# MCU.net
KiCad netlist of a schematic drawn in Altium Designer
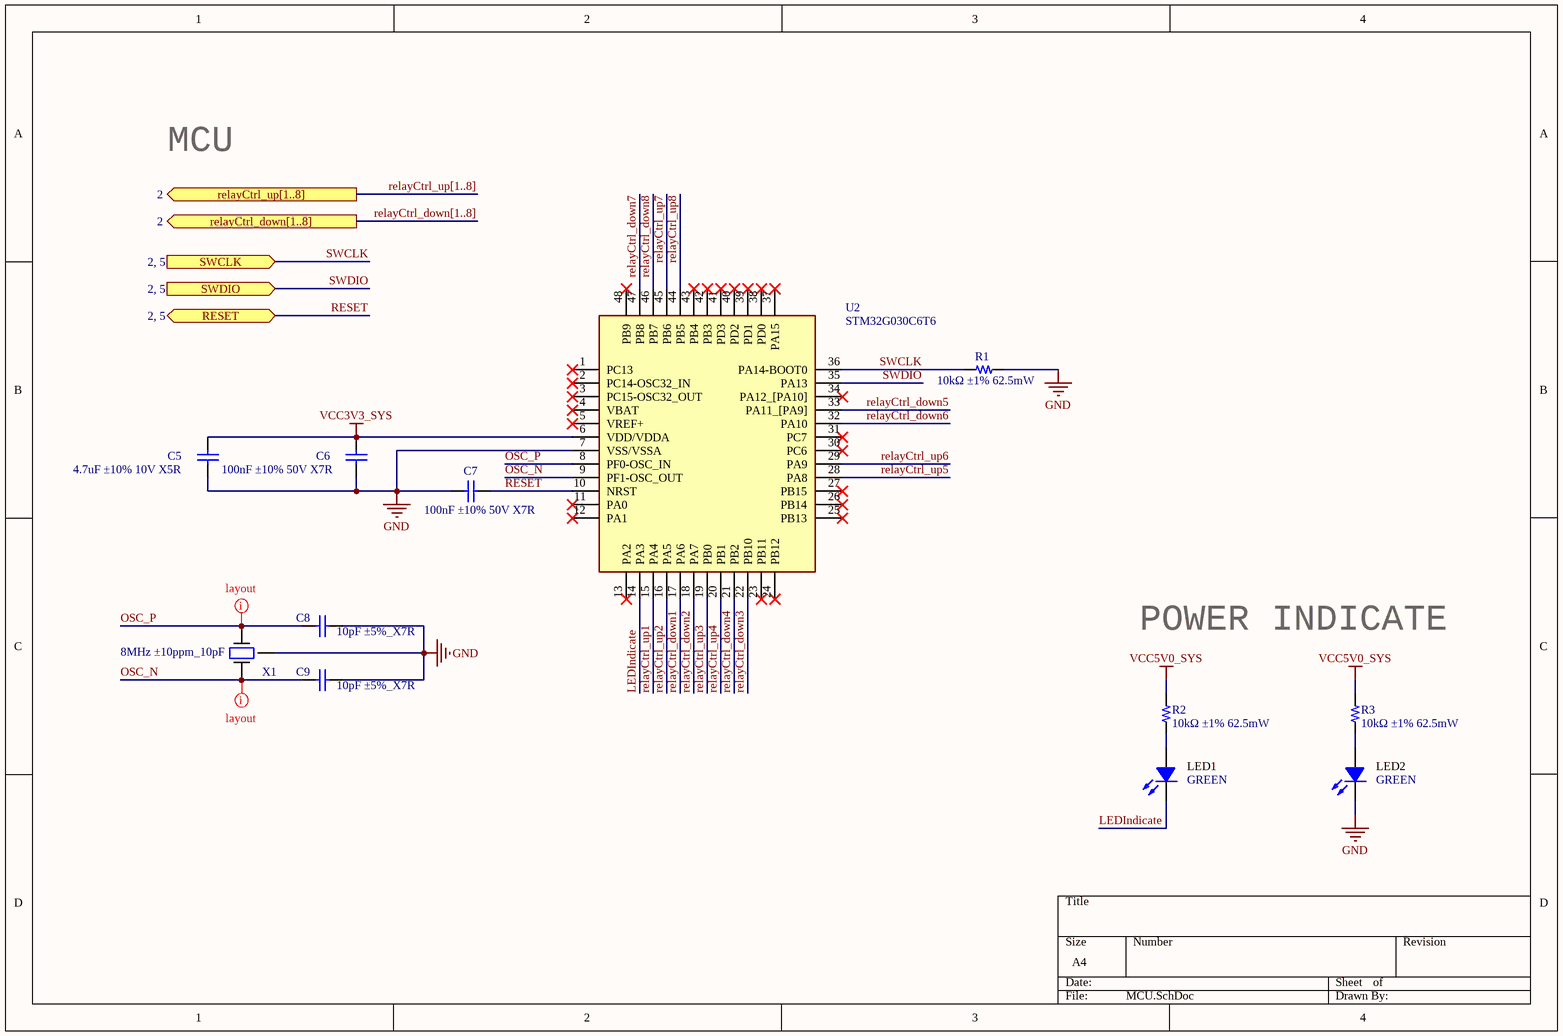
[diagram p0: MCU.SchDoc]

(export (version "E")
  (design (tool "Eeschema 10.0.6"))
  (components
    (comp (ref "C5")
      (value "4.7uF ±10% 10V X5R")
      (footprint "C0402")
      (description "CL05A475KP5NRNC")
      (fields (field (name "PUBLISHER") "Altium Limited"))
      (libsource (lib "Component") (part "Cap"))
    )
    (comp (ref "C6")
      (value "100nF ±10% 50V X7R")
      (footprint "C0402")
      (description "CL05B104KO5NNNC")
      (fields (field (name "PUBLISHER") "Altium Limited"))
      (libsource (lib "Component") (part "Cap"))
    )
    (comp (ref "C7")
      (value "100nF ±10% 50V X7R")
      (footprint "C0402")
      (description "CL05B104KO5NNNC")
      (fields (field (name "PUBLISHER") "Altium Limited"))
      (libsource (lib "Component") (part "Cap"))
    )
    (comp (ref "C8")
      (value "10pF ±5%_X7R")
      (footprint "C0402")
      (description "Capacitor")
      (fields (field (name "PUBLISHER") "Altium Limited"))
      (libsource (lib "Component") (part "Cap"))
    )
    (comp (ref "C9")
      (value "10pF ±5%_X7R")
      (footprint "C0402")
      (description "Capacitor")
      (fields (field (name "PUBLISHER") "Altium Limited"))
      (libsource (lib "Component") (part "Cap"))
    )
    (comp (ref "LED1")
      (value "GREEN")
      (footprint "LED0603-RD")
      (fields
        (field (name "MANUFACTURER") "EVERLIGHT(亿光)")
        (field (name "MANUFACTURER PART") "17-21SURC/S530-A2/TR8")
      )
      (libsource (lib "Component") (part "LED"))
    )
    (comp (ref "LED2")
      (value "GREEN")
      (footprint "LED0603-RD")
      (fields
        (field (name "MANUFACTURER") "EVERLIGHT(亿光)")
        (field (name "MANUFACTURER PART") "17-21SURC/S530-A2/TR8")
      )
      (libsource (lib "Component") (part "LED"))
    )
    (comp (ref "R1")
      (value "10kΩ ±1% 62.5mW")
      (footprint "R0402")
      (description "0402WGF1002TCE")
      (libsource (lib "Device") (part "R-0603"))
    )
    (comp (ref "R2")
      (value "10kΩ ±1% 62.5mW")
      (footprint "R0402")
      (description "0402WGF1002TCE")
      (libsource (lib "Device") (part "R-0603"))
    )
    (comp (ref "R3")
      (value "10kΩ ±1% 62.5mW")
      (footprint "R0402")
      (description "0402WGF1002TCE")
      (libsource (lib "Device") (part "R-0603"))
    )
    (comp (ref "U2")
      (value "STM32G030C6T6")
      (footprint "SamacSys:QFP50P900X900X160-48N")
      (description "Integrated Circuit")
      (fields (field (name "MOUSER PART NUMBER") "511-STM32G030C6T6"))
      (libsource (lib "*") (part "STM32G030C6T6"))
    )
    (comp (ref "X1")
      (value "8MHz ±10ppm_10pF")
      (footprint "CRYSTAL_3225")
      (description "Crystal 8MHz ±10ppm 10pF 200 Ohm -10°C ~ 60°C Surface Mount 4-SMD, No Lead (DFN, LCC)")
      (fields
        (field (name "MANUFACTURER") "Abracon LLC")
        (field (name "MANUFACTURER PART NUMBER") "ABM3B-8.000MHZ-10-1-U-T")
      )
      (libsource (lib "Component") (part "CRYSTAL"))
    )
  )
  (nets
    (net (code "1") (name "/LEDIndicate") (class "Default")
      (node (ref "LED1") (pin "2") (pinfunction "K_2") (pintype "passive"))
      (node (ref "U2") (pin "14") (pinfunction "PA3_14") (pintype "passive"))
    )
    (net (code "2") (name "/OSC_N") (class "Default")
      (node (ref "C9") (pin "1") (pinfunction "1_1") (pintype "passive"))
      (node (ref "U2") (pin "9") (pinfunction "PF1-OSC_OUT_9") (pintype "passive"))
      (node (ref "X1") (pin "1") (pintype "passive"))
    )
    (net (code "3") (name "/OSC_P") (class "Default")
      (node (ref "C8") (pin "1") (pinfunction "1_1") (pintype "passive"))
      (node (ref "U2") (pin "8") (pinfunction "PF0-OSC_IN_8") (pintype "passive"))
      (node (ref "X1") (pin "3") (pintype "passive"))
    )
    (net (code "4") (name "/RESET") (class "Default")
      (node (ref "C7") (pin "2") (pinfunction "2_2") (pintype "passive"))
      (node (ref "U2") (pin "10") (pinfunction "NRST_10") (pintype "passive"))
    )
    (net (code "5") (name "/SWCLK") (class "Default")
      (node (ref "R1") (pin "2") (pinfunction "2_2") (pintype "passive"))
      (node (ref "U2") (pin "36") (pinfunction "PA14-BOOT0_36") (pintype "passive"))
    )
    (net (code "6") (name "/SWDIO") (class "Default")
      (node (ref "U2") (pin "35") (pinfunction "PA13_35") (pintype "passive"))
    )
    (net (code "7") (name "/relayCtrl_down1") (class "Default")
      (node (ref "U2") (pin "17") (pinfunction "PA6_17") (pintype "passive"))
    )
    (net (code "8") (name "/relayCtrl_down2") (class "Default")
      (node (ref "U2") (pin "18") (pinfunction "PA7_18") (pintype "passive"))
    )
    (net (code "9") (name "/relayCtrl_down3") (class "Default")
      (node (ref "U2") (pin "22") (pinfunction "PB10_22") (pintype "passive"))
    )
    (net (code "10") (name "/relayCtrl_down4") (class "Default")
      (node (ref "U2") (pin "21") (pinfunction "PB2_21") (pintype "passive"))
    )
    (net (code "11") (name "/relayCtrl_down5") (class "Default")
      (node (ref "U2") (pin "33") (pinfunction "PA11_[PA9]_33") (pintype "passive"))
    )
    (net (code "12") (name "/relayCtrl_down6") (class "Default")
      (node (ref "U2") (pin "32") (pinfunction "PA10_32") (pintype "passive"))
    )
    (net (code "13") (name "/relayCtrl_down7") (class "Default")
      (node (ref "U2") (pin "47") (pinfunction "PB8_47") (pintype "passive"))
    )
    (net (code "14") (name "/relayCtrl_down8") (class "Default")
      (node (ref "U2") (pin "46") (pinfunction "PB7_46") (pintype "passive"))
    )
    (net (code "16") (name "/relayCtrl_up1") (class "Default")
      (node (ref "U2") (pin "15") (pinfunction "PA4_15") (pintype "passive"))
    )
    (net (code "17") (name "/relayCtrl_up2") (class "Default")
      (node (ref "U2") (pin "16") (pinfunction "PA5_16") (pintype "passive"))
    )
    (net (code "18") (name "/relayCtrl_up3") (class "Default")
      (node (ref "U2") (pin "19") (pinfunction "PB0_19") (pintype "passive"))
    )
    (net (code "19") (name "/relayCtrl_up4") (class "Default")
      (node (ref "U2") (pin "20") (pinfunction "PB1_20") (pintype "passive"))
    )
    (net (code "20") (name "/relayCtrl_up5") (class "Default")
      (node (ref "U2") (pin "28") (pinfunction "PA8_28") (pintype "passive"))
    )
    (net (code "21") (name "/relayCtrl_up6") (class "Default")
      (node (ref "U2") (pin "29") (pinfunction "PA9_29") (pintype "passive"))
    )
    (net (code "22") (name "/relayCtrl_up7") (class "Default")
      (node (ref "U2") (pin "45") (pinfunction "PB6_45") (pintype "passive"))
    )
    (net (code "23") (name "/relayCtrl_up8") (class "Default")
      (node (ref "U2") (pin "44") (pinfunction "PB5_44") (pintype "passive"))
    )
    (net (code "25") (name "GND") (class "Default")
      (node (ref "C5") (pin "1") (pinfunction "1_1") (pintype "passive"))
      (node (ref "C6") (pin "1") (pinfunction "1_1") (pintype "passive"))
      (node (ref "C7") (pin "1") (pinfunction "1_1") (pintype "passive"))
      (node (ref "C8") (pin "2") (pinfunction "2_2") (pintype "passive"))
      (node (ref "C9") (pin "2") (pinfunction "2_2") (pintype "passive"))
      (node (ref "LED2") (pin "2") (pinfunction "K_2") (pintype "passive"))
      (node (ref "R1") (pin "1") (pinfunction "1_1") (pintype "passive"))
      (node (ref "U2") (pin "7") (pinfunction "VSS/VSSA_7") (pintype "passive"))
      (node (ref "X1") (pin "G") (pintype "passive"))
    )
    (net (code "26") (name "Net-(LED1-A)") (class "Default")
      (node (ref "LED1") (pin "1") (pinfunction "A_1") (pintype "passive"))
      (node (ref "R2") (pin "2") (pinfunction "2_2") (pintype "passive"))
    )
    (net (code "27") (name "Net-(LED2-A)") (class "Default")
      (node (ref "LED2") (pin "1") (pinfunction "A_1") (pintype "passive"))
      (node (ref "R3") (pin "2") (pinfunction "2_2") (pintype "passive"))
    )
    (net (code "28") (name "VCC3V3_SYS") (class "Default")
      (node (ref "C5") (pin "2") (pinfunction "2_2") (pintype "passive"))
      (node (ref "C6") (pin "2") (pinfunction "2_2") (pintype "passive"))
      (node (ref "U2") (pin "6") (pinfunction "VDD/VDDA_6") (pintype "passive"))
    )
    (net (code "29") (name "VCC5V0_SYS") (class "Default")
      (node (ref "R2") (pin "1") (pinfunction "1_1") (pintype "passive"))
      (node (ref "R3") (pin "1") (pinfunction "1_1") (pintype "passive"))
    )
    (net (code "30") (name "unconnected-(U2-PA0-Pad11)") (class "Default")
      (node (ref "U2") (pin "11") (pinfunction "PA0_11") (pintype "passive+no_connect"))
    )
    (net (code "31") (name "unconnected-(U2-PA1-Pad12)") (class "Default")
      (node (ref "U2") (pin "12") (pinfunction "PA1_12") (pintype "passive+no_connect"))
    )
    (net (code "32") (name "unconnected-(U2-PA2-Pad13)") (class "Default")
      (node (ref "U2") (pin "13") (pinfunction "PA2_13") (pintype "passive+no_connect"))
    )
    (net (code "33") (name "unconnected-(U2-PA12_[PA10]-Pad34)") (class "Default")
      (node (ref "U2") (pin "34") (pinfunction "PA12_[PA10]_34") (pintype "passive+no_connect"))
    )
    (net (code "34") (name "unconnected-(U2-PA15-Pad37)") (class "Default")
      (node (ref "U2") (pin "37") (pinfunction "PA15_37") (pintype "passive+no_connect"))
    )
    (net (code "35") (name "unconnected-(U2-PB3-Pad42)") (class "Default")
      (node (ref "U2") (pin "42") (pinfunction "PB3_42") (pintype "passive+no_connect"))
    )
    (net (code "36") (name "unconnected-(U2-PB4-Pad43)") (class "Default")
      (node (ref "U2") (pin "43") (pinfunction "PB4_43") (pintype "passive+no_connect"))
    )
    (net (code "37") (name "unconnected-(U2-PB9-Pad48)") (class "Default")
      (node (ref "U2") (pin "48") (pinfunction "PB9_48") (pintype "passive+no_connect"))
    )
    (net (code "38") (name "unconnected-(U2-PB11-Pad23)") (class "Default")
      (node (ref "U2") (pin "23") (pinfunction "PB11_23") (pintype "passive+no_connect"))
    )
    (net (code "39") (name "unconnected-(U2-PB12-Pad24)") (class "Default")
      (node (ref "U2") (pin "24") (pinfunction "PB12_24") (pintype "passive+no_connect"))
    )
    (net (code "40") (name "unconnected-(U2-PB13-Pad25)") (class "Default")
      (node (ref "U2") (pin "25") (pinfunction "PB13_25") (pintype "passive+no_connect"))
    )
    (net (code "41") (name "unconnected-(U2-PB14-Pad26)") (class "Default")
      (node (ref "U2") (pin "26") (pinfunction "PB14_26") (pintype "passive+no_connect"))
    )
    (net (code "42") (name "unconnected-(U2-PB15-Pad27)") (class "Default")
      (node (ref "U2") (pin "27") (pinfunction "PB15_27") (pintype "passive+no_connect"))
    )
    (net (code "43") (name "unconnected-(U2-PC6-Pad30)") (class "Default")
      (node (ref "U2") (pin "30") (pinfunction "PC6_30") (pintype "passive+no_connect"))
    )
    (net (code "44") (name "unconnected-(U2-PC7-Pad31)") (class "Default")
      (node (ref "U2") (pin "31") (pinfunction "PC7_31") (pintype "passive+no_connect"))
    )
    (net (code "45") (name "unconnected-(U2-PC13-Pad1)") (class "Default")
      (node (ref "U2") (pin "1") (pinfunction "PC13_1") (pintype "passive+no_connect"))
    )
    (net (code "46") (name "unconnected-(U2-PC14-OSC32_IN-Pad2)") (class "Default")
      (node (ref "U2") (pin "2") (pinfunction "PC14-OSC32_IN_2") (pintype "passive+no_connect"))
    )
    (net (code "47") (name "unconnected-(U2-PC15-OSC32_OUT-Pad3)") (class "Default")
      (node (ref "U2") (pin "3") (pinfunction "PC15-OSC32_OUT_3") (pintype "passive+no_connect"))
    )
    (net (code "48") (name "unconnected-(U2-PD0-Pad38)") (class "Default")
      (node (ref "U2") (pin "38") (pinfunction "PD0_38") (pintype "passive+no_connect"))
    )
    (net (code "49") (name "unconnected-(U2-PD1-Pad39)") (class "Default")
      (node (ref "U2") (pin "39") (pinfunction "PD1_39") (pintype "passive+no_connect"))
    )
    (net (code "50") (name "unconnected-(U2-PD2-Pad40)") (class "Default")
      (node (ref "U2") (pin "40") (pinfunction "PD2_40") (pintype "passive+no_connect"))
    )
    (net (code "51") (name "unconnected-(U2-PD3-Pad41)") (class "Default")
      (node (ref "U2") (pin "41") (pinfunction "PD3_41") (pintype "passive+no_connect"))
    )
    (net (code "52") (name "unconnected-(U2-VBAT-Pad4)") (class "Default")
      (node (ref "U2") (pin "4") (pinfunction "VBAT_4") (pintype "passive+no_connect"))
    )
    (net (code "53") (name "unconnected-(U2-VREF+-Pad5)") (class "Default")
      (node (ref "U2") (pin "5") (pinfunction "VREF+_5") (pintype "passive+no_connect"))
    )
  )
)
